# tb_project_ir_blaster_maxi_wemos_revA.net
KiCad netlist of a schematic drawn in EAGLE
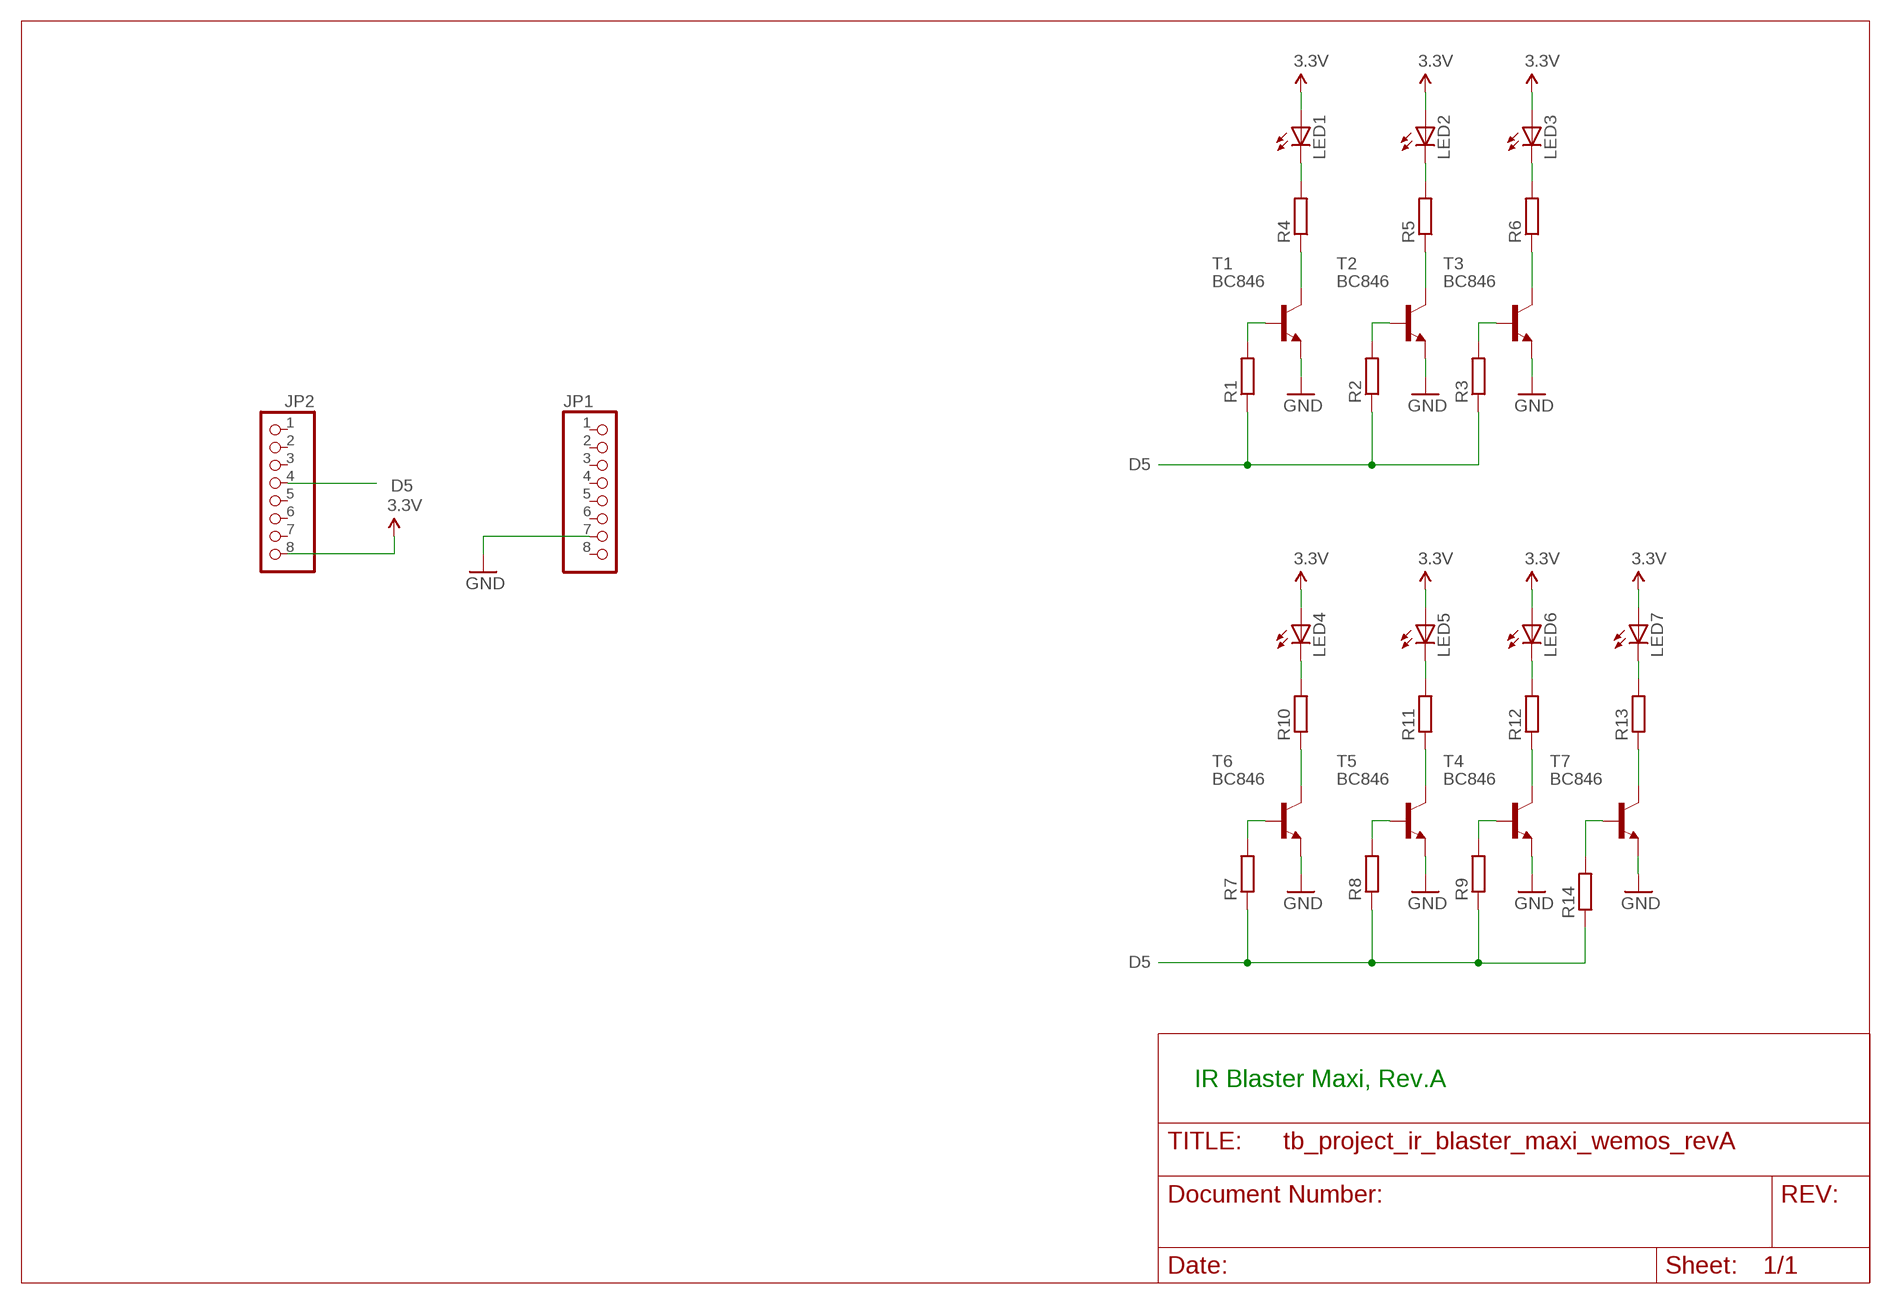
[diagram p0: schematic, sheet 1]

(export (version "E")
  (design (tool "Eeschema 10.0.6"))
  (components
    (comp (ref "JP1")
      (value "PINHD-1X8")
      (footprint "eagle-import:1X08")
      (libsource (lib "eagle-import") (part "PINHD-1X8"))
    )
    (comp (ref "JP2")
      (value "PINHD-1X8")
      (footprint "eagle-import:1X08")
      (libsource (lib "eagle-import") (part "PINHD-1X8"))
    )
    (comp (ref "LED1")
      (value "LED5MM")
      (footprint "eagle-import:LED5MM")
      (libsource (lib "eagle-import") (part "LED5MM"))
    )
    (comp (ref "LED2")
      (value "LED5MM")
      (footprint "eagle-import:LED5MM")
      (libsource (lib "eagle-import") (part "LED5MM"))
    )
    (comp (ref "LED3")
      (value "LED5MM")
      (footprint "eagle-import:LED5MM")
      (libsource (lib "eagle-import") (part "LED5MM"))
    )
    (comp (ref "LED4")
      (value "LED5MM")
      (footprint "eagle-import:LED5MM")
      (libsource (lib "eagle-import") (part "LED5MM"))
    )
    (comp (ref "LED5")
      (value "LED5MM")
      (footprint "eagle-import:LED5MM")
      (libsource (lib "eagle-import") (part "LED5MM"))
    )
    (comp (ref "LED6")
      (value "LED5MM")
      (footprint "eagle-import:LED5MM")
      (libsource (lib "eagle-import") (part "LED5MM"))
    )
    (comp (ref "LED7")
      (value "LED5MM")
      (footprint "eagle-import:LED5MM")
      (libsource (lib "eagle-import") (part "LED5MM"))
    )
    (comp (ref "R1")
      (value "R-EU_R1206")
      (footprint "eagle-import:R1206")
      (libsource (lib "eagle-import") (part "R-EU_R1206"))
    )
    (comp (ref "R2")
      (value "R-EU_R1206")
      (footprint "eagle-import:R1206")
      (libsource (lib "eagle-import") (part "R-EU_R1206"))
    )
    (comp (ref "R3")
      (value "R-EU_R1206")
      (footprint "eagle-import:R1206")
      (libsource (lib "eagle-import") (part "R-EU_R1206"))
    )
    (comp (ref "R4")
      (value "R-EU_R1206")
      (footprint "eagle-import:R1206")
      (libsource (lib "eagle-import") (part "R-EU_R1206"))
    )
    (comp (ref "R5")
      (value "R-EU_R1206")
      (footprint "eagle-import:R1206")
      (libsource (lib "eagle-import") (part "R-EU_R1206"))
    )
    (comp (ref "R6")
      (value "R-EU_R1206")
      (footprint "eagle-import:R1206")
      (libsource (lib "eagle-import") (part "R-EU_R1206"))
    )
    (comp (ref "R7")
      (value "R-EU_R1206")
      (footprint "eagle-import:R1206")
      (libsource (lib "eagle-import") (part "R-EU_R1206"))
    )
    (comp (ref "R8")
      (value "R-EU_R1206")
      (footprint "eagle-import:R1206")
      (libsource (lib "eagle-import") (part "R-EU_R1206"))
    )
    (comp (ref "R9")
      (value "R-EU_R1206")
      (footprint "eagle-import:R1206")
      (libsource (lib "eagle-import") (part "R-EU_R1206"))
    )
    (comp (ref "R10")
      (value "R-EU_R1206")
      (footprint "eagle-import:R1206")
      (libsource (lib "eagle-import") (part "R-EU_R1206"))
    )
    (comp (ref "R11")
      (value "R-EU_R1206")
      (footprint "eagle-import:R1206")
      (libsource (lib "eagle-import") (part "R-EU_R1206"))
    )
    (comp (ref "R12")
      (value "R-EU_R1206")
      (footprint "eagle-import:R1206")
      (libsource (lib "eagle-import") (part "R-EU_R1206"))
    )
    (comp (ref "R13")
      (value "R-EU_R1206")
      (footprint "eagle-import:R1206")
      (libsource (lib "eagle-import") (part "R-EU_R1206"))
    )
    (comp (ref "R14")
      (value "R-EU_R1206")
      (footprint "eagle-import:R1206")
      (libsource (lib "eagle-import") (part "R-EU_R1206"))
    )
    (comp (ref "T1")
      (value "BC846")
      (footprint "eagle-import:SOT23")
      (libsource (lib "eagle-import") (part "BC846"))
    )
    (comp (ref "T2")
      (value "BC846")
      (footprint "eagle-import:SOT23")
      (libsource (lib "eagle-import") (part "BC846"))
    )
    (comp (ref "T3")
      (value "BC846")
      (footprint "eagle-import:SOT23")
      (libsource (lib "eagle-import") (part "BC846"))
    )
    (comp (ref "T4")
      (value "BC846")
      (footprint "eagle-import:SOT23")
      (libsource (lib "eagle-import") (part "BC846"))
    )
    (comp (ref "T5")
      (value "BC846")
      (footprint "eagle-import:SOT23")
      (libsource (lib "eagle-import") (part "BC846"))
    )
    (comp (ref "T6")
      (value "BC846")
      (footprint "eagle-import:SOT23")
      (libsource (lib "eagle-import") (part "BC846"))
    )
    (comp (ref "T7")
      (value "BC846")
      (footprint "eagle-import:SOT23")
      (libsource (lib "eagle-import") (part "BC846"))
    )
  )
  (nets
    (net (code "1") (name "/D5") (class "Default")
      (node (ref "JP2") (pin "4") (pinfunction "4_4") (pintype "passive"))
      (node (ref "R1") (pin "1") (pinfunction "1_1") (pintype "passive"))
      (node (ref "R14") (pin "1") (pinfunction "1_1") (pintype "passive"))
      (node (ref "R2") (pin "1") (pinfunction "1_1") (pintype "passive"))
      (node (ref "R3") (pin "1") (pinfunction "1_1") (pintype "passive"))
      (node (ref "R7") (pin "1") (pinfunction "1_1") (pintype "passive"))
      (node (ref "R8") (pin "1") (pinfunction "1_1") (pintype "passive"))
      (node (ref "R9") (pin "1") (pinfunction "1_1") (pintype "passive"))
    )
    (net (code "2") (name "3.3V") (class "Default")
      (node (ref "JP2") (pin "8") (pinfunction "8_8") (pintype "passive"))
      (node (ref "LED1") (pin "A") (pinfunction "A_A") (pintype "passive"))
      (node (ref "LED2") (pin "A") (pinfunction "A_A") (pintype "passive"))
      (node (ref "LED3") (pin "A") (pinfunction "A_A") (pintype "passive"))
      (node (ref "LED4") (pin "A") (pinfunction "A_A") (pintype "passive"))
      (node (ref "LED5") (pin "A") (pinfunction "A_A") (pintype "passive"))
      (node (ref "LED6") (pin "A") (pinfunction "A_A") (pintype "passive"))
      (node (ref "LED7") (pin "A") (pinfunction "A_A") (pintype "passive"))
    )
    (net (code "3") (name "GND") (class "Default")
      (node (ref "JP1") (pin "7") (pinfunction "7_7") (pintype "passive"))
      (node (ref "T1") (pin "2") (pinfunction "E_2") (pintype "passive"))
      (node (ref "T2") (pin "2") (pinfunction "E_2") (pintype "passive"))
      (node (ref "T3") (pin "2") (pinfunction "E_2") (pintype "passive"))
      (node (ref "T4") (pin "2") (pinfunction "E_2") (pintype "passive"))
      (node (ref "T5") (pin "2") (pinfunction "E_2") (pintype "passive"))
      (node (ref "T6") (pin "2") (pinfunction "E_2") (pintype "passive"))
      (node (ref "T7") (pin "2") (pinfunction "E_2") (pintype "passive"))
    )
    (net (code "4") (name "Net-(LED1-C)") (class "Default")
      (node (ref "LED1") (pin "K") (pinfunction "C_K") (pintype "passive"))
      (node (ref "R4") (pin "2") (pinfunction "2_2") (pintype "passive"))
    )
    (net (code "5") (name "Net-(LED2-C)") (class "Default")
      (node (ref "LED2") (pin "K") (pinfunction "C_K") (pintype "passive"))
      (node (ref "R5") (pin "2") (pinfunction "2_2") (pintype "passive"))
    )
    (net (code "6") (name "Net-(LED3-C)") (class "Default")
      (node (ref "LED3") (pin "K") (pinfunction "C_K") (pintype "passive"))
      (node (ref "R6") (pin "2") (pinfunction "2_2") (pintype "passive"))
    )
    (net (code "7") (name "Net-(LED4-C)") (class "Default")
      (node (ref "LED4") (pin "K") (pinfunction "C_K") (pintype "passive"))
      (node (ref "R10") (pin "2") (pinfunction "2_2") (pintype "passive"))
    )
    (net (code "8") (name "Net-(LED5-C)") (class "Default")
      (node (ref "LED5") (pin "K") (pinfunction "C_K") (pintype "passive"))
      (node (ref "R11") (pin "2") (pinfunction "2_2") (pintype "passive"))
    )
    (net (code "9") (name "Net-(LED6-C)") (class "Default")
      (node (ref "LED6") (pin "K") (pinfunction "C_K") (pintype "passive"))
      (node (ref "R12") (pin "2") (pinfunction "2_2") (pintype "passive"))
    )
    (net (code "10") (name "Net-(LED7-C)") (class "Default")
      (node (ref "LED7") (pin "K") (pinfunction "C_K") (pintype "passive"))
      (node (ref "R13") (pin "2") (pinfunction "2_2") (pintype "passive"))
    )
    (net (code "11") (name "Net-(T1-B)") (class "Default")
      (node (ref "R1") (pin "2") (pinfunction "2_2") (pintype "passive"))
      (node (ref "T1") (pin "1") (pinfunction "B_1") (pintype "passive"))
    )
    (net (code "12") (name "Net-(T1-C)") (class "Default")
      (node (ref "R4") (pin "1") (pinfunction "1_1") (pintype "passive"))
      (node (ref "T1") (pin "3") (pinfunction "C_3") (pintype "passive"))
    )
    (net (code "13") (name "Net-(T2-B)") (class "Default")
      (node (ref "R2") (pin "2") (pinfunction "2_2") (pintype "passive"))
      (node (ref "T2") (pin "1") (pinfunction "B_1") (pintype "passive"))
    )
    (net (code "14") (name "Net-(T2-C)") (class "Default")
      (node (ref "R5") (pin "1") (pinfunction "1_1") (pintype "passive"))
      (node (ref "T2") (pin "3") (pinfunction "C_3") (pintype "passive"))
    )
    (net (code "15") (name "Net-(T3-B)") (class "Default")
      (node (ref "R3") (pin "2") (pinfunction "2_2") (pintype "passive"))
      (node (ref "T3") (pin "1") (pinfunction "B_1") (pintype "passive"))
    )
    (net (code "16") (name "Net-(T3-C)") (class "Default")
      (node (ref "R6") (pin "1") (pinfunction "1_1") (pintype "passive"))
      (node (ref "T3") (pin "3") (pinfunction "C_3") (pintype "passive"))
    )
    (net (code "17") (name "Net-(T4-B)") (class "Default")
      (node (ref "R9") (pin "2") (pinfunction "2_2") (pintype "passive"))
      (node (ref "T4") (pin "1") (pinfunction "B_1") (pintype "passive"))
    )
    (net (code "18") (name "Net-(T4-C)") (class "Default")
      (node (ref "R12") (pin "1") (pinfunction "1_1") (pintype "passive"))
      (node (ref "T4") (pin "3") (pinfunction "C_3") (pintype "passive"))
    )
    (net (code "19") (name "Net-(T5-B)") (class "Default")
      (node (ref "R8") (pin "2") (pinfunction "2_2") (pintype "passive"))
      (node (ref "T5") (pin "1") (pinfunction "B_1") (pintype "passive"))
    )
    (net (code "20") (name "Net-(T5-C)") (class "Default")
      (node (ref "R11") (pin "1") (pinfunction "1_1") (pintype "passive"))
      (node (ref "T5") (pin "3") (pinfunction "C_3") (pintype "passive"))
    )
    (net (code "21") (name "Net-(T6-B)") (class "Default")
      (node (ref "R7") (pin "2") (pinfunction "2_2") (pintype "passive"))
      (node (ref "T6") (pin "1") (pinfunction "B_1") (pintype "passive"))
    )
    (net (code "22") (name "Net-(T6-C)") (class "Default")
      (node (ref "R10") (pin "1") (pinfunction "1_1") (pintype "passive"))
      (node (ref "T6") (pin "3") (pinfunction "C_3") (pintype "passive"))
    )
    (net (code "23") (name "Net-(T7-B)") (class "Default")
      (node (ref "R14") (pin "2") (pinfunction "2_2") (pintype "passive"))
      (node (ref "T7") (pin "1") (pinfunction "B_1") (pintype "passive"))
    )
    (net (code "24") (name "Net-(T7-C)") (class "Default")
      (node (ref "R13") (pin "1") (pinfunction "1_1") (pintype "passive"))
      (node (ref "T7") (pin "3") (pinfunction "C_3") (pintype "passive"))
    )
    (net (code "25") (name "unconnected-(JP1-Pad1)") (class "Default")
      (node (ref "JP1") (pin "1") (pinfunction "1_1") (pintype "passive"))
    )
    (net (code "26") (name "unconnected-(JP1-Pad2)") (class "Default")
      (node (ref "JP1") (pin "2") (pinfunction "2_2") (pintype "passive"))
    )
    (net (code "27") (name "unconnected-(JP1-Pad3)") (class "Default")
      (node (ref "JP1") (pin "3") (pinfunction "3_3") (pintype "passive"))
    )
    (net (code "28") (name "unconnected-(JP1-Pad4)") (class "Default")
      (node (ref "JP1") (pin "4") (pinfunction "4_4") (pintype "passive"))
    )
    (net (code "29") (name "unconnected-(JP1-Pad5)") (class "Default")
      (node (ref "JP1") (pin "5") (pinfunction "5_5") (pintype "passive"))
    )
    (net (code "30") (name "unconnected-(JP1-Pad6)") (class "Default")
      (node (ref "JP1") (pin "6") (pinfunction "6_6") (pintype "passive"))
    )
    (net (code "31") (name "unconnected-(JP1-Pad8)") (class "Default")
      (node (ref "JP1") (pin "8") (pinfunction "8_8") (pintype "passive"))
    )
    (net (code "32") (name "unconnected-(JP2-Pad1)") (class "Default")
      (node (ref "JP2") (pin "1") (pinfunction "1_1") (pintype "passive"))
    )
    (net (code "33") (name "unconnected-(JP2-Pad2)") (class "Default")
      (node (ref "JP2") (pin "2") (pinfunction "2_2") (pintype "passive"))
    )
    (net (code "34") (name "unconnected-(JP2-Pad3)") (class "Default")
      (node (ref "JP2") (pin "3") (pinfunction "3_3") (pintype "passive"))
    )
    (net (code "35") (name "unconnected-(JP2-Pad5)") (class "Default")
      (node (ref "JP2") (pin "5") (pinfunction "5_5") (pintype "passive"))
    )
    (net (code "36") (name "unconnected-(JP2-Pad6)") (class "Default")
      (node (ref "JP2") (pin "6") (pinfunction "6_6") (pintype "passive"))
    )
    (net (code "37") (name "unconnected-(JP2-Pad7)") (class "Default")
      (node (ref "JP2") (pin "7") (pinfunction "7_7") (pintype "passive"))
    )
  )
)
